# led_final.net
KiCad netlist of a schematic drawn in EAGLE
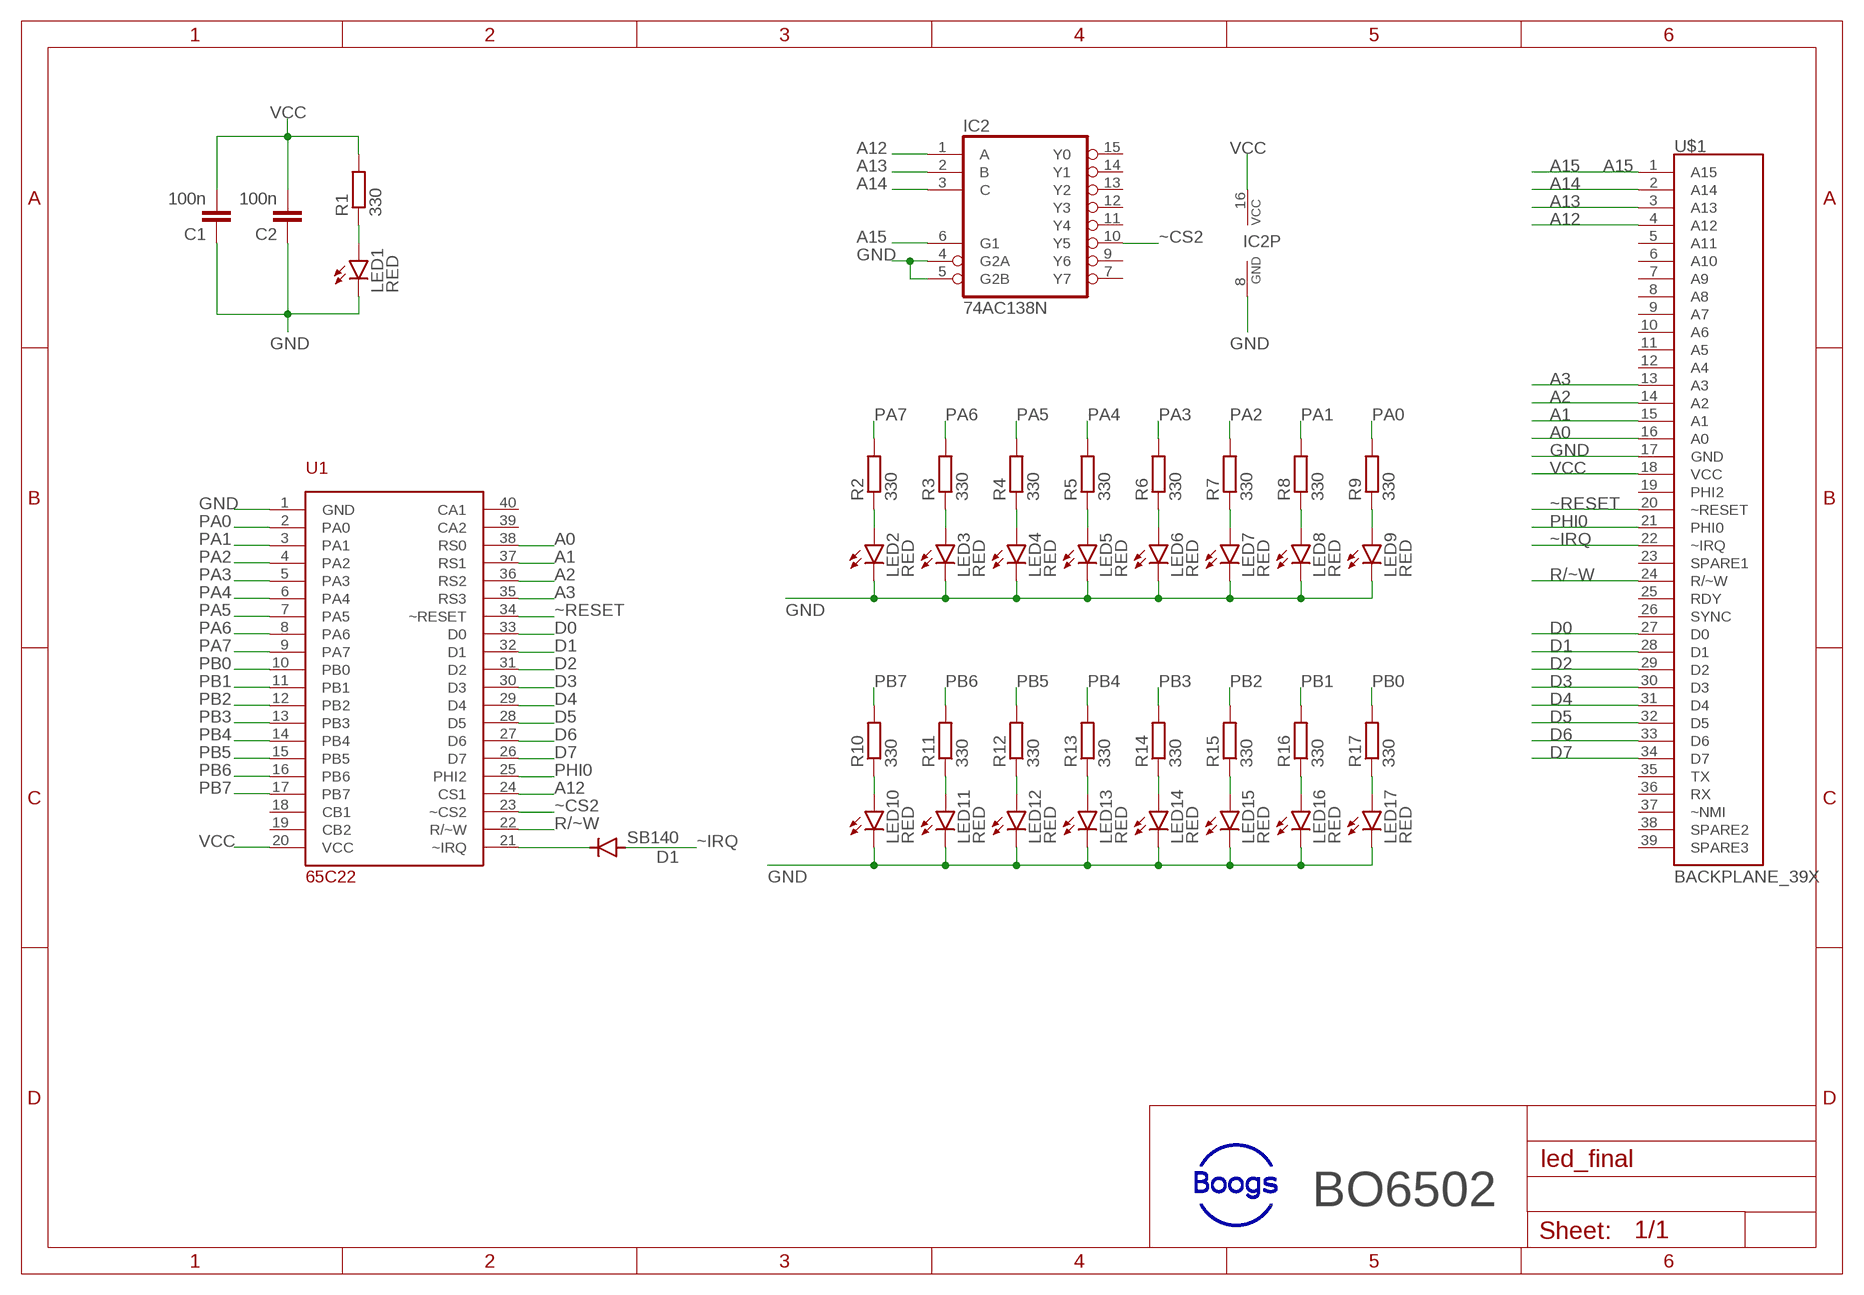
[diagram p0: schematic, sheet 1]

(export (version "E")
  (design (tool "Eeschema 10.0.6"))
  (components
    (comp (ref "C1")
      (value "100n")
      (footprint "eagle-import:C025-025X050")
      (libsource (lib "eagle-import") (part "C-EU025-025X050"))
    )
    (comp (ref "C2")
      (value "100n")
      (footprint "eagle-import:C025-025X050")
      (libsource (lib "eagle-import") (part "C-EU025-025X050"))
    )
    (comp (ref "D1")
      (value "SB140")
      (footprint "eagle-import:DO41-10")
      (libsource (lib "eagle-import") (part "1N4004"))
    )
    (comp (ref "IC2")
      (value "74AC138N")
      (footprint "eagle-import:DIL16")
      (libsource (lib "eagle-import") (part "74138NAC"))
    )
    (comp (ref "LED1")
      (value "RED")
      (footprint "eagle-import:LED5MM")
      (libsource (lib "eagle-import") (part "LED5MM"))
    )
    (comp (ref "LED2")
      (value "RED")
      (footprint "eagle-import:LED5MM")
      (libsource (lib "eagle-import") (part "LED5MM"))
    )
    (comp (ref "LED3")
      (value "RED")
      (footprint "eagle-import:LED5MM")
      (libsource (lib "eagle-import") (part "LED5MM"))
    )
    (comp (ref "LED4")
      (value "RED")
      (footprint "eagle-import:LED5MM")
      (libsource (lib "eagle-import") (part "LED5MM"))
    )
    (comp (ref "LED5")
      (value "RED")
      (footprint "eagle-import:LED5MM")
      (libsource (lib "eagle-import") (part "LED5MM"))
    )
    (comp (ref "LED6")
      (value "RED")
      (footprint "eagle-import:LED5MM")
      (libsource (lib "eagle-import") (part "LED5MM"))
    )
    (comp (ref "LED7")
      (value "RED")
      (footprint "eagle-import:LED5MM")
      (libsource (lib "eagle-import") (part "LED5MM"))
    )
    (comp (ref "LED8")
      (value "RED")
      (footprint "eagle-import:LED5MM")
      (libsource (lib "eagle-import") (part "LED5MM"))
    )
    (comp (ref "LED9")
      (value "RED")
      (footprint "eagle-import:LED5MM")
      (libsource (lib "eagle-import") (part "LED5MM"))
    )
    (comp (ref "LED10")
      (value "RED")
      (footprint "eagle-import:LED5MM")
      (libsource (lib "eagle-import") (part "LED5MM"))
    )
    (comp (ref "LED11")
      (value "RED")
      (footprint "eagle-import:LED5MM")
      (libsource (lib "eagle-import") (part "LED5MM"))
    )
    (comp (ref "LED12")
      (value "RED")
      (footprint "eagle-import:LED5MM")
      (libsource (lib "eagle-import") (part "LED5MM"))
    )
    (comp (ref "LED13")
      (value "RED")
      (footprint "eagle-import:LED5MM")
      (libsource (lib "eagle-import") (part "LED5MM"))
    )
    (comp (ref "LED14")
      (value "RED")
      (footprint "eagle-import:LED5MM")
      (libsource (lib "eagle-import") (part "LED5MM"))
    )
    (comp (ref "LED15")
      (value "RED")
      (footprint "eagle-import:LED5MM")
      (libsource (lib "eagle-import") (part "LED5MM"))
    )
    (comp (ref "LED16")
      (value "RED")
      (footprint "eagle-import:LED5MM")
      (libsource (lib "eagle-import") (part "LED5MM"))
    )
    (comp (ref "LED17")
      (value "RED")
      (footprint "eagle-import:LED5MM")
      (libsource (lib "eagle-import") (part "LED5MM"))
    )
    (comp (ref "R1")
      (value "330")
      (footprint "eagle-import:0207_10")
      (libsource (lib "eagle-import") (part "R-EU_0207/10"))
    )
    (comp (ref "R2")
      (value "330")
      (footprint "eagle-import:0207_10")
      (libsource (lib "eagle-import") (part "R-EU_0207/10"))
    )
    (comp (ref "R3")
      (value "330")
      (footprint "eagle-import:0207_10")
      (libsource (lib "eagle-import") (part "R-EU_0207/10"))
    )
    (comp (ref "R4")
      (value "330")
      (footprint "eagle-import:0207_10")
      (libsource (lib "eagle-import") (part "R-EU_0207/10"))
    )
    (comp (ref "R5")
      (value "330")
      (footprint "eagle-import:0207_10")
      (libsource (lib "eagle-import") (part "R-EU_0207/10"))
    )
    (comp (ref "R6")
      (value "330")
      (footprint "eagle-import:0207_10")
      (libsource (lib "eagle-import") (part "R-EU_0207/10"))
    )
    (comp (ref "R7")
      (value "330")
      (footprint "eagle-import:0207_10")
      (libsource (lib "eagle-import") (part "R-EU_0207/10"))
    )
    (comp (ref "R8")
      (value "330")
      (footprint "eagle-import:0207_10")
      (libsource (lib "eagle-import") (part "R-EU_0207/10"))
    )
    (comp (ref "R9")
      (value "330")
      (footprint "eagle-import:0207_10")
      (libsource (lib "eagle-import") (part "R-EU_0207/10"))
    )
    (comp (ref "R10")
      (value "330")
      (footprint "eagle-import:0207_10")
      (libsource (lib "eagle-import") (part "R-EU_0207/10"))
    )
    (comp (ref "R11")
      (value "330")
      (footprint "eagle-import:0207_10")
      (libsource (lib "eagle-import") (part "R-EU_0207/10"))
    )
    (comp (ref "R12")
      (value "330")
      (footprint "eagle-import:0207_10")
      (libsource (lib "eagle-import") (part "R-EU_0207/10"))
    )
    (comp (ref "R13")
      (value "330")
      (footprint "eagle-import:0207_10")
      (libsource (lib "eagle-import") (part "R-EU_0207/10"))
    )
    (comp (ref "R14")
      (value "330")
      (footprint "eagle-import:0207_10")
      (libsource (lib "eagle-import") (part "R-EU_0207/10"))
    )
    (comp (ref "R15")
      (value "330")
      (footprint "eagle-import:0207_10")
      (libsource (lib "eagle-import") (part "R-EU_0207/10"))
    )
    (comp (ref "R16")
      (value "330")
      (footprint "eagle-import:0207_10")
      (libsource (lib "eagle-import") (part "R-EU_0207/10"))
    )
    (comp (ref "R17")
      (value "330")
      (footprint "eagle-import:0207_10")
      (libsource (lib "eagle-import") (part "R-EU_0207/10"))
    )
    (comp (ref "U$1")
      (value "BACKPLANE_39X")
      (footprint "eagle-import:BP_39X")
      (fields (field (name "A15") "A15"))
      (libsource (lib "eagle-import") (part "BACKPLANE_39X"))
    )
    (comp (ref "U1")
      (value "65C22")
      (footprint "eagle-import:DIL40")
      (libsource (lib "eagle-import") (part "65C22"))
    )
  )
  (nets
    (net (code "1") (name "/A0") (class "Default")
      (node (ref "U$1") (pin "16") (pinfunction "A0_16") (pintype "bidirectional"))
      (node (ref "U1") (pin "38") (pinfunction "RS0_38") (pintype "bidirectional"))
    )
    (net (code "2") (name "/A1") (class "Default")
      (node (ref "U$1") (pin "15") (pinfunction "A1_15") (pintype "bidirectional"))
      (node (ref "U1") (pin "37") (pinfunction "RS1_37") (pintype "bidirectional"))
    )
    (net (code "3") (name "/A2") (class "Default")
      (node (ref "U$1") (pin "14") (pinfunction "A2_14") (pintype "bidirectional"))
      (node (ref "U1") (pin "36") (pinfunction "RS2_36") (pintype "bidirectional"))
    )
    (net (code "4") (name "/A3") (class "Default")
      (node (ref "U$1") (pin "13") (pinfunction "A3_13") (pintype "bidirectional"))
      (node (ref "U1") (pin "35") (pinfunction "RS3_35") (pintype "bidirectional"))
    )
    (net (code "5") (name "/A12") (class "Default")
      (node (ref "IC2") (pin "1") (pinfunction "A_1") (pintype "input"))
      (node (ref "U$1") (pin "4") (pinfunction "A12_4") (pintype "bidirectional"))
      (node (ref "U1") (pin "24") (pinfunction "CS1_24") (pintype "bidirectional"))
    )
    (net (code "6") (name "/A13") (class "Default")
      (node (ref "IC2") (pin "2") (pinfunction "B_2") (pintype "input"))
      (node (ref "U$1") (pin "3") (pinfunction "A13_3") (pintype "bidirectional"))
    )
    (net (code "7") (name "/A14") (class "Default")
      (node (ref "IC2") (pin "3") (pinfunction "C_3") (pintype "input"))
      (node (ref "U$1") (pin "2") (pinfunction "A14_2") (pintype "bidirectional"))
    )
    (net (code "8") (name "/A15") (class "Default")
      (node (ref "IC2") (pin "6") (pinfunction "G1_6") (pintype "input"))
      (node (ref "U$1") (pin "1") (pinfunction "A15_1") (pintype "bidirectional"))
    )
    (net (code "9") (name "/D0") (class "Default")
      (node (ref "U$1") (pin "27") (pinfunction "D0_27") (pintype "bidirectional"))
      (node (ref "U1") (pin "33") (pinfunction "D0_33") (pintype "bidirectional"))
    )
    (net (code "10") (name "/D1") (class "Default")
      (node (ref "U$1") (pin "28") (pinfunction "D1_28") (pintype "bidirectional"))
      (node (ref "U1") (pin "32") (pinfunction "D1_32") (pintype "bidirectional"))
    )
    (net (code "11") (name "/D2") (class "Default")
      (node (ref "U$1") (pin "29") (pinfunction "D2_29") (pintype "bidirectional"))
      (node (ref "U1") (pin "31") (pinfunction "D2_31") (pintype "bidirectional"))
    )
    (net (code "12") (name "/D3") (class "Default")
      (node (ref "U$1") (pin "30") (pinfunction "D3_30") (pintype "bidirectional"))
      (node (ref "U1") (pin "30") (pinfunction "D3_30") (pintype "bidirectional"))
    )
    (net (code "13") (name "/D4") (class "Default")
      (node (ref "U$1") (pin "31") (pinfunction "D4_31") (pintype "bidirectional"))
      (node (ref "U1") (pin "29") (pinfunction "D4_29") (pintype "bidirectional"))
    )
    (net (code "14") (name "/D5") (class "Default")
      (node (ref "U$1") (pin "32") (pinfunction "D5_32") (pintype "bidirectional"))
      (node (ref "U1") (pin "28") (pinfunction "D5_28") (pintype "bidirectional"))
    )
    (net (code "15") (name "/D6") (class "Default")
      (node (ref "U$1") (pin "33") (pinfunction "D6_33") (pintype "bidirectional"))
      (node (ref "U1") (pin "27") (pinfunction "D6_27") (pintype "bidirectional"))
    )
    (net (code "16") (name "/D7") (class "Default")
      (node (ref "U$1") (pin "34") (pinfunction "D7_34") (pintype "bidirectional"))
      (node (ref "U1") (pin "26") (pinfunction "D7_26") (pintype "bidirectional"))
    )
    (net (code "17") (name "/GND") (class "Default")
      (node (ref "C1") (pin "1") (pinfunction "1_1") (pintype "passive"))
      (node (ref "C2") (pin "1") (pinfunction "1_1") (pintype "passive"))
      (node (ref "IC2") (pin "4") (pinfunction "G2A_4") (pintype "input"))
      (node (ref "IC2") (pin "5") (pinfunction "G2B_5") (pintype "input"))
      (node (ref "IC2") (pin "8") (pinfunction "GND_8") (pintype "power_in"))
      (node (ref "LED1") (pin "K") (pinfunction "C_K") (pintype "passive"))
      (node (ref "LED10") (pin "K") (pinfunction "C_K") (pintype "passive"))
      (node (ref "LED11") (pin "K") (pinfunction "C_K") (pintype "passive"))
      (node (ref "LED12") (pin "K") (pinfunction "C_K") (pintype "passive"))
      (node (ref "LED13") (pin "K") (pinfunction "C_K") (pintype "passive"))
      (node (ref "LED14") (pin "K") (pinfunction "C_K") (pintype "passive"))
      (node (ref "LED15") (pin "K") (pinfunction "C_K") (pintype "passive"))
      (node (ref "LED16") (pin "K") (pinfunction "C_K") (pintype "passive"))
      (node (ref "LED17") (pin "K") (pinfunction "C_K") (pintype "passive"))
      (node (ref "LED2") (pin "K") (pinfunction "C_K") (pintype "passive"))
      (node (ref "LED3") (pin "K") (pinfunction "C_K") (pintype "passive"))
      (node (ref "LED4") (pin "K") (pinfunction "C_K") (pintype "passive"))
      (node (ref "LED5") (pin "K") (pinfunction "C_K") (pintype "passive"))
      (node (ref "LED6") (pin "K") (pinfunction "C_K") (pintype "passive"))
      (node (ref "LED7") (pin "K") (pinfunction "C_K") (pintype "passive"))
      (node (ref "LED8") (pin "K") (pinfunction "C_K") (pintype "passive"))
      (node (ref "LED9") (pin "K") (pinfunction "C_K") (pintype "passive"))
      (node (ref "U$1") (pin "17") (pinfunction "GND_17") (pintype "bidirectional"))
      (node (ref "U1") (pin "1") (pinfunction "GND_1") (pintype "bidirectional"))
    )
    (net (code "18") (name "/PA0") (class "Default")
      (node (ref "R9") (pin "2") (pinfunction "2_2") (pintype "passive"))
      (node (ref "U1") (pin "2") (pinfunction "PA0_2") (pintype "bidirectional"))
    )
    (net (code "19") (name "/PA1") (class "Default")
      (node (ref "R8") (pin "2") (pinfunction "2_2") (pintype "passive"))
      (node (ref "U1") (pin "3") (pinfunction "PA1_3") (pintype "bidirectional"))
    )
    (net (code "20") (name "/PA2") (class "Default")
      (node (ref "R7") (pin "2") (pinfunction "2_2") (pintype "passive"))
      (node (ref "U1") (pin "4") (pinfunction "PA2_4") (pintype "bidirectional"))
    )
    (net (code "21") (name "/PA3") (class "Default")
      (node (ref "R6") (pin "2") (pinfunction "2_2") (pintype "passive"))
      (node (ref "U1") (pin "5") (pinfunction "PA3_5") (pintype "bidirectional"))
    )
    (net (code "22") (name "/PA4") (class "Default")
      (node (ref "R5") (pin "2") (pinfunction "2_2") (pintype "passive"))
      (node (ref "U1") (pin "6") (pinfunction "PA4_6") (pintype "bidirectional"))
    )
    (net (code "23") (name "/PA5") (class "Default")
      (node (ref "R4") (pin "2") (pinfunction "2_2") (pintype "passive"))
      (node (ref "U1") (pin "7") (pinfunction "PA5_7") (pintype "bidirectional"))
    )
    (net (code "24") (name "/PA6") (class "Default")
      (node (ref "R3") (pin "2") (pinfunction "2_2") (pintype "passive"))
      (node (ref "U1") (pin "8") (pinfunction "PA6_8") (pintype "bidirectional"))
    )
    (net (code "25") (name "/PA7") (class "Default")
      (node (ref "R2") (pin "2") (pinfunction "2_2") (pintype "passive"))
      (node (ref "U1") (pin "9") (pinfunction "PA7_9") (pintype "bidirectional"))
    )
    (net (code "26") (name "/PB0") (class "Default")
      (node (ref "R17") (pin "2") (pinfunction "2_2") (pintype "passive"))
      (node (ref "U1") (pin "10") (pinfunction "PB0_10") (pintype "bidirectional"))
    )
    (net (code "27") (name "/PB1") (class "Default")
      (node (ref "R16") (pin "2") (pinfunction "2_2") (pintype "passive"))
      (node (ref "U1") (pin "11") (pinfunction "PB1_11") (pintype "bidirectional"))
    )
    (net (code "28") (name "/PB2") (class "Default")
      (node (ref "R15") (pin "2") (pinfunction "2_2") (pintype "passive"))
      (node (ref "U1") (pin "12") (pinfunction "PB2_12") (pintype "bidirectional"))
    )
    (net (code "29") (name "/PB3") (class "Default")
      (node (ref "R14") (pin "2") (pinfunction "2_2") (pintype "passive"))
      (node (ref "U1") (pin "13") (pinfunction "PB3_13") (pintype "bidirectional"))
    )
    (net (code "30") (name "/PB4") (class "Default")
      (node (ref "R13") (pin "2") (pinfunction "2_2") (pintype "passive"))
      (node (ref "U1") (pin "14") (pinfunction "PB4_14") (pintype "bidirectional"))
    )
    (net (code "31") (name "/PB5") (class "Default")
      (node (ref "R12") (pin "2") (pinfunction "2_2") (pintype "passive"))
      (node (ref "U1") (pin "15") (pinfunction "PB5_15") (pintype "bidirectional"))
    )
    (net (code "32") (name "/PB6") (class "Default")
      (node (ref "R11") (pin "2") (pinfunction "2_2") (pintype "passive"))
      (node (ref "U1") (pin "16") (pinfunction "PB6_16") (pintype "bidirectional"))
    )
    (net (code "33") (name "/PB7") (class "Default")
      (node (ref "R10") (pin "2") (pinfunction "2_2") (pintype "passive"))
      (node (ref "U1") (pin "17") (pinfunction "PB7_17") (pintype "bidirectional"))
    )
    (net (code "34") (name "/PHI0") (class "Default")
      (node (ref "U$1") (pin "21") (pinfunction "PHI0_21") (pintype "bidirectional"))
      (node (ref "U1") (pin "25") (pinfunction "PHI2_25") (pintype "bidirectional"))
    )
    (net (code "35") (name "/R{slash}~{W}") (class "Default")
      (node (ref "U$1") (pin "24") (pinfunction "R/~{W}_24") (pintype "bidirectional"))
      (node (ref "U1") (pin "22") (pinfunction "R/~{W}_22") (pintype "bidirectional"))
    )
    (net (code "36") (name "/VCC") (class "Default")
      (node (ref "C1") (pin "2") (pinfunction "2_2") (pintype "passive"))
      (node (ref "C2") (pin "2") (pinfunction "2_2") (pintype "passive"))
      (node (ref "IC2") (pin "16") (pinfunction "VCC_16") (pintype "power_in"))
      (node (ref "R1") (pin "2") (pinfunction "2_2") (pintype "passive"))
      (node (ref "U$1") (pin "18") (pinfunction "VCC_18") (pintype "bidirectional"))
      (node (ref "U1") (pin "20") (pinfunction "VCC_20") (pintype "bidirectional"))
    )
    (net (code "37") (name "/~{CS2}") (class "Default")
      (node (ref "IC2") (pin "10") (pinfunction "Y5_10") (pintype "output"))
      (node (ref "U1") (pin "23") (pinfunction "~{CS2}_23") (pintype "bidirectional"))
    )
    (net (code "38") (name "/~{IRQ}") (class "Default")
      (node (ref "D1") (pin "A") (pinfunction "A_A") (pintype "passive"))
      (node (ref "U$1") (pin "22") (pinfunction "~{IRQ}_22") (pintype "bidirectional"))
    )
    (net (code "39") (name "/~{RESET}") (class "Default")
      (node (ref "U$1") (pin "20") (pinfunction "~{RESET}_20") (pintype "bidirectional"))
      (node (ref "U1") (pin "34") (pinfunction "~{RESET}_34") (pintype "bidirectional"))
    )
    (net (code "40") (name "Net-(LED1-PadA)") (class "Default")
      (node (ref "LED1") (pin "A") (pinfunction "A_A") (pintype "passive"))
      (node (ref "R1") (pin "1") (pinfunction "1_1") (pintype "passive"))
    )
    (net (code "41") (name "Net-(LED2-PadA)") (class "Default")
      (node (ref "LED2") (pin "A") (pinfunction "A_A") (pintype "passive"))
      (node (ref "R2") (pin "1") (pinfunction "1_1") (pintype "passive"))
    )
    (net (code "42") (name "Net-(LED3-PadA)") (class "Default")
      (node (ref "LED3") (pin "A") (pinfunction "A_A") (pintype "passive"))
      (node (ref "R3") (pin "1") (pinfunction "1_1") (pintype "passive"))
    )
    (net (code "43") (name "Net-(LED4-PadA)") (class "Default")
      (node (ref "LED4") (pin "A") (pinfunction "A_A") (pintype "passive"))
      (node (ref "R4") (pin "1") (pinfunction "1_1") (pintype "passive"))
    )
    (net (code "44") (name "Net-(LED5-PadA)") (class "Default")
      (node (ref "LED5") (pin "A") (pinfunction "A_A") (pintype "passive"))
      (node (ref "R5") (pin "1") (pinfunction "1_1") (pintype "passive"))
    )
    (net (code "45") (name "Net-(LED6-PadA)") (class "Default")
      (node (ref "LED6") (pin "A") (pinfunction "A_A") (pintype "passive"))
      (node (ref "R6") (pin "1") (pinfunction "1_1") (pintype "passive"))
    )
    (net (code "46") (name "Net-(LED7-PadA)") (class "Default")
      (node (ref "LED7") (pin "A") (pinfunction "A_A") (pintype "passive"))
      (node (ref "R7") (pin "1") (pinfunction "1_1") (pintype "passive"))
    )
    (net (code "47") (name "Net-(LED8-PadA)") (class "Default")
      (node (ref "LED8") (pin "A") (pinfunction "A_A") (pintype "passive"))
      (node (ref "R8") (pin "1") (pinfunction "1_1") (pintype "passive"))
    )
    (net (code "48") (name "Net-(LED9-PadA)") (class "Default")
      (node (ref "LED9") (pin "A") (pinfunction "A_A") (pintype "passive"))
      (node (ref "R9") (pin "1") (pinfunction "1_1") (pintype "passive"))
    )
    (net (code "49") (name "Net-(LED10-PadA)") (class "Default")
      (node (ref "LED10") (pin "A") (pinfunction "A_A") (pintype "passive"))
      (node (ref "R10") (pin "1") (pinfunction "1_1") (pintype "passive"))
    )
    (net (code "50") (name "Net-(LED11-PadA)") (class "Default")
      (node (ref "LED11") (pin "A") (pinfunction "A_A") (pintype "passive"))
      (node (ref "R11") (pin "1") (pinfunction "1_1") (pintype "passive"))
    )
    (net (code "51") (name "Net-(LED12-PadA)") (class "Default")
      (node (ref "LED12") (pin "A") (pinfunction "A_A") (pintype "passive"))
      (node (ref "R12") (pin "1") (pinfunction "1_1") (pintype "passive"))
    )
    (net (code "52") (name "Net-(LED13-PadA)") (class "Default")
      (node (ref "LED13") (pin "A") (pinfunction "A_A") (pintype "passive"))
      (node (ref "R13") (pin "1") (pinfunction "1_1") (pintype "passive"))
    )
    (net (code "53") (name "Net-(LED14-PadA)") (class "Default")
      (node (ref "LED14") (pin "A") (pinfunction "A_A") (pintype "passive"))
      (node (ref "R14") (pin "1") (pinfunction "1_1") (pintype "passive"))
    )
    (net (code "54") (name "Net-(LED15-PadA)") (class "Default")
      (node (ref "LED15") (pin "A") (pinfunction "A_A") (pintype "passive"))
      (node (ref "R15") (pin "1") (pinfunction "1_1") (pintype "passive"))
    )
    (net (code "55") (name "Net-(LED16-PadA)") (class "Default")
      (node (ref "LED16") (pin "A") (pinfunction "A_A") (pintype "passive"))
      (node (ref "R16") (pin "1") (pinfunction "1_1") (pintype "passive"))
    )
    (net (code "56") (name "Net-(LED17-PadA)") (class "Default")
      (node (ref "LED17") (pin "A") (pinfunction "A_A") (pintype "passive"))
      (node (ref "R17") (pin "1") (pinfunction "1_1") (pintype "passive"))
    )
    (net (code "57") (name "Net-(U1-~{IRQ})") (class "Default")
      (node (ref "D1") (pin "C") (pinfunction "C_C") (pintype "passive"))
      (node (ref "U1") (pin "21") (pinfunction "~{IRQ}_21") (pintype "bidirectional"))
    )
    (net (code "58") (name "unconnected-(IC2A-Y0-Pad15)") (class "Default")
      (node (ref "IC2") (pin "15") (pinfunction "Y0_15") (pintype "output"))
    )
    (net (code "59") (name "unconnected-(IC2A-Y1-Pad14)") (class "Default")
      (node (ref "IC2") (pin "14") (pinfunction "Y1_14") (pintype "output"))
    )
    (net (code "60") (name "unconnected-(IC2A-Y2-Pad13)") (class "Default")
      (node (ref "IC2") (pin "13") (pinfunction "Y2_13") (pintype "output"))
    )
    (net (code "61") (name "unconnected-(IC2A-Y3-Pad12)") (class "Default")
      (node (ref "IC2") (pin "12") (pinfunction "Y3_12") (pintype "output"))
    )
    (net (code "62") (name "unconnected-(IC2A-Y4-Pad11)") (class "Default")
      (node (ref "IC2") (pin "11") (pinfunction "Y4_11") (pintype "output"))
    )
    (net (code "63") (name "unconnected-(IC2A-Y6-Pad9)") (class "Default")
      (node (ref "IC2") (pin "9") (pinfunction "Y6_9") (pintype "output"))
    )
    (net (code "64") (name "unconnected-(IC2A-Y7-Pad7)") (class "Default")
      (node (ref "IC2") (pin "7") (pinfunction "Y7_7") (pintype "output"))
    )
    (net (code "65") (name "unconnected-(U$1-A4-Pad12)") (class "Default")
      (node (ref "U$1") (pin "12") (pinfunction "A4_12") (pintype "bidirectional"))
    )
    (net (code "66") (name "unconnected-(U$1-A5-Pad11)") (class "Default")
      (node (ref "U$1") (pin "11") (pinfunction "A5_11") (pintype "bidirectional"))
    )
    (net (code "67") (name "unconnected-(U$1-A6-Pad10)") (class "Default")
      (node (ref "U$1") (pin "10") (pinfunction "A6_10") (pintype "bidirectional"))
    )
    (net (code "68") (name "unconnected-(U$1-A7-Pad9)") (class "Default")
      (node (ref "U$1") (pin "9") (pinfunction "A7_9") (pintype "bidirectional"))
    )
    (net (code "69") (name "unconnected-(U$1-A8-Pad8)") (class "Default")
      (node (ref "U$1") (pin "8") (pinfunction "A8_8") (pintype "bidirectional"))
    )
    (net (code "70") (name "unconnected-(U$1-A9-Pad7)") (class "Default")
      (node (ref "U$1") (pin "7") (pinfunction "A9_7") (pintype "bidirectional"))
    )
    (net (code "71") (name "unconnected-(U$1-A10-Pad6)") (class "Default")
      (node (ref "U$1") (pin "6") (pinfunction "A10_6") (pintype "bidirectional"))
    )
    (net (code "72") (name "unconnected-(U$1-A11-Pad5)") (class "Default")
      (node (ref "U$1") (pin "5") (pinfunction "A11_5") (pintype "bidirectional"))
    )
    (net (code "73") (name "unconnected-(U$1-PHI2-Pad19)") (class "Default")
      (node (ref "U$1") (pin "19") (pinfunction "PHI2_19") (pintype "bidirectional"))
    )
    (net (code "74") (name "unconnected-(U$1-RDY-Pad25)") (class "Default")
      (node (ref "U$1") (pin "25") (pinfunction "RDY_25") (pintype "bidirectional"))
    )
    (net (code "75") (name "unconnected-(U$1-RX-Pad36)") (class "Default")
      (node (ref "U$1") (pin "36") (pinfunction "RX_36") (pintype "bidirectional"))
    )
    (net (code "76") (name "unconnected-(U$1-SPARE1-Pad23)") (class "Default")
      (node (ref "U$1") (pin "23") (pinfunction "SPARE1_23") (pintype "bidirectional"))
    )
    (net (code "77") (name "unconnected-(U$1-SPARE2-Pad38)") (class "Default")
      (node (ref "U$1") (pin "38") (pinfunction "SPARE2_38") (pintype "bidirectional"))
    )
    (net (code "78") (name "unconnected-(U$1-SPARE3-Pad39)") (class "Default")
      (node (ref "U$1") (pin "39") (pinfunction "SPARE3_39") (pintype "bidirectional"))
    )
    (net (code "79") (name "unconnected-(U$1-SYNC-Pad26)") (class "Default")
      (node (ref "U$1") (pin "26") (pinfunction "SYNC_26") (pintype "bidirectional"))
    )
    (net (code "80") (name "unconnected-(U$1-TX-Pad35)") (class "Default")
      (node (ref "U$1") (pin "35") (pinfunction "TX_35") (pintype "bidirectional"))
    )
    (net (code "81") (name "unconnected-(U$1-~{NMI}-Pad37)") (class "Default")
      (node (ref "U$1") (pin "37") (pinfunction "~{NMI}_37") (pintype "bidirectional"))
    )
    (net (code "82") (name "unconnected-(U1-CA1-Pad40)") (class "Default")
      (node (ref "U1") (pin "40") (pinfunction "CA1_40") (pintype "bidirectional"))
    )
    (net (code "83") (name "unconnected-(U1-CA2-Pad39)") (class "Default")
      (node (ref "U1") (pin "39") (pinfunction "CA2_39") (pintype "bidirectional"))
    )
    (net (code "84") (name "unconnected-(U1-CB1-Pad18)") (class "Default")
      (node (ref "U1") (pin "18") (pinfunction "CB1_18") (pintype "bidirectional"))
    )
    (net (code "85") (name "unconnected-(U1-CB2-Pad19)") (class "Default")
      (node (ref "U1") (pin "19") (pinfunction "CB2_19") (pintype "bidirectional"))
    )
  )
)
